# dynext_v2_0.net
KiCad netlist of a schematic drawn in EAGLE
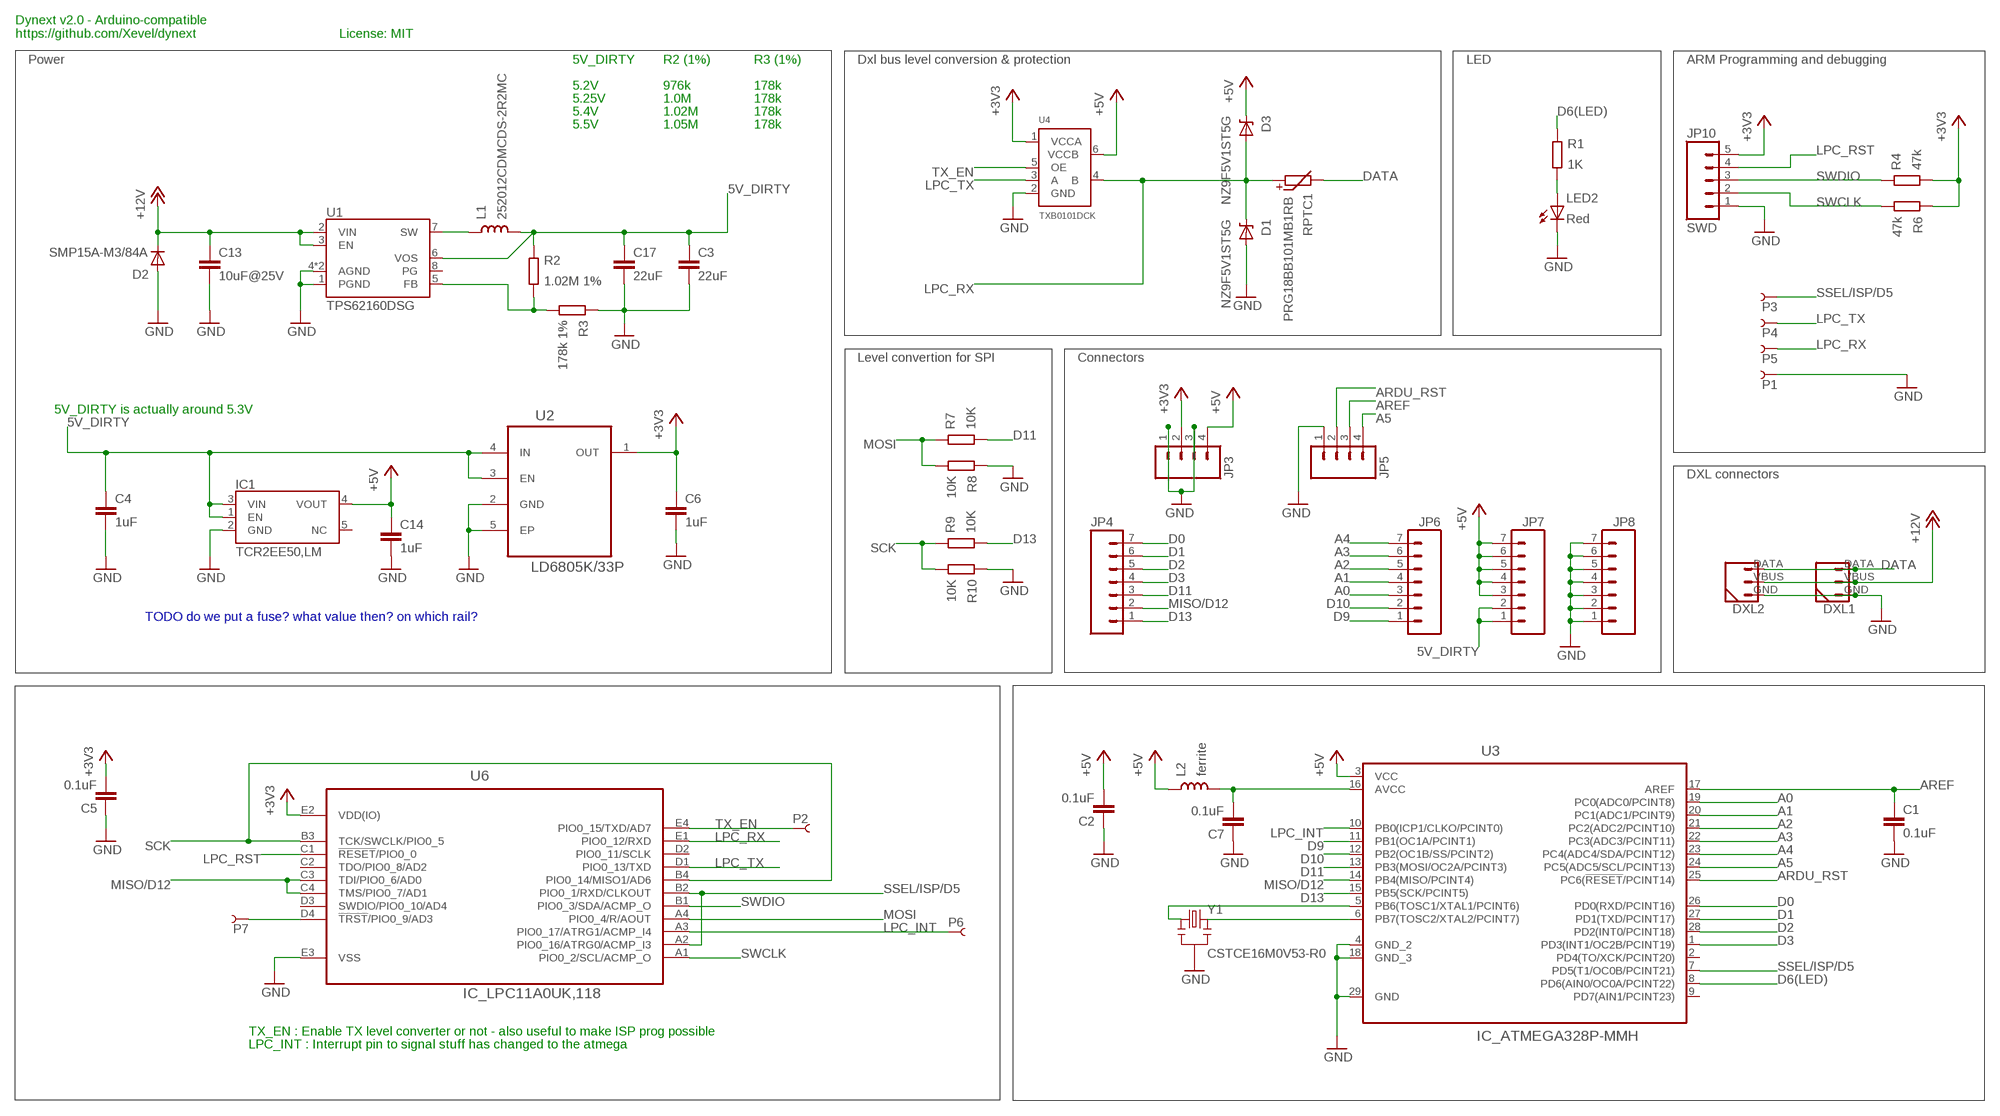
[diagram p0: schematic, sheet 1]

(export (version "E")
  (design (tool "Eeschema 10.0.6"))
  (components
    (comp (ref "C1")
      (value "0.1uF")
      (footprint "eagle-import:0201_N")
      (libsource (lib "eagle-import") (part "C0201"))
    )
    (comp (ref "C2")
      (value "0.1uF")
      (footprint "eagle-import:0201_N")
      (libsource (lib "eagle-import") (part "C0201"))
    )
    (comp (ref "C3")
      (value "22uF")
      (footprint "eagle-import:1206_N")
      (libsource (lib "eagle-import") (part "C1206"))
    )
    (comp (ref "C4")
      (value "1uF")
      (footprint "eagle-import:0402_N")
      (libsource (lib "eagle-import") (part "C0402"))
    )
    (comp (ref "C5")
      (value "0.1uF")
      (footprint "eagle-import:0201_N")
      (libsource (lib "eagle-import") (part "C0201"))
    )
    (comp (ref "C6")
      (value "1uF")
      (footprint "eagle-import:0402_N")
      (libsource (lib "eagle-import") (part "C0402"))
    )
    (comp (ref "C7")
      (value "0.1uF")
      (footprint "eagle-import:0201_N")
      (libsource (lib "eagle-import") (part "C0201"))
    )
    (comp (ref "C13")
      (value "10uF@25V")
      (footprint "eagle-import:0805_N")
      (libsource (lib "eagle-import") (part "C0805"))
    )
    (comp (ref "C14")
      (value "1uF")
      (footprint "eagle-import:0402_N")
      (libsource (lib "eagle-import") (part "C0402"))
    )
    (comp (ref "C17")
      (value "22uF")
      (footprint "eagle-import:1206_N")
      (libsource (lib "eagle-import") (part "C1206"))
    )
    (comp (ref "D1")
      (value "NZ9F5V1ST5G")
      (footprint "eagle-import:SOD-923_N")
      (libsource (lib "eagle-import") (part "DIODE_ZENER-923"))
    )
    (comp (ref "D2")
      (value "SMP15A-M3/84A")
      (footprint "eagle-import:DO-220AA")
      (libsource (lib "eagle-import") (part "DIODE-SMP"))
    )
    (comp (ref "D3")
      (value "NZ9F5V1ST5G")
      (footprint "eagle-import:SOD-923_N")
      (libsource (lib "eagle-import") (part "DIODE_ZENER-923"))
    )
    (comp (ref "DXL1")
      (value "DYNAMIXEL_3POS-R")
      (footprint "eagle-import:DYNAMIXEL_3POS_RIGHT")
      (libsource (lib "eagle-import") (part "DYNAMIXEL_3POS-R"))
    )
    (comp (ref "DXL2")
      (value "DYNAMIXEL_3POS-R")
      (footprint "eagle-import:DYNAMIXEL_3POS_RIGHT")
      (libsource (lib "eagle-import") (part "DYNAMIXEL_3POS-R"))
    )
    (comp (ref "IC1")
      (value "TCR2EE50,LM")
      (footprint "eagle-import:SOT50P160X60-5N")
      (libsource (lib "eagle-import") (part "IC_TCR2EEESV"))
    )
    (comp (ref "JP3")
      (value "M041X04_NO_SILK")
      (footprint "eagle-import:1X04_NO_SILK")
      (libsource (lib "eagle-import") (part "M041X04_NO_SILK"))
    )
    (comp (ref "JP4")
      (value "M07NO_SILK")
      (footprint "eagle-import:1X07_NO_SILK")
      (libsource (lib "eagle-import") (part "M07NO_SILK"))
    )
    (comp (ref "JP5")
      (value "M041X04_NO_SILK")
      (footprint "eagle-import:1X04_NO_SILK")
      (libsource (lib "eagle-import") (part "M041X04_NO_SILK"))
    )
    (comp (ref "JP6")
      (value "M07NO_SILK")
      (footprint "eagle-import:1X07_NO_SILK")
      (libsource (lib "eagle-import") (part "M07NO_SILK"))
    )
    (comp (ref "JP7")
      (value "M07NO_SILK")
      (footprint "eagle-import:1X07_NO_SILK")
      (libsource (lib "eagle-import") (part "M07NO_SILK"))
    )
    (comp (ref "JP8")
      (value "M07SQUARE_ALL")
      (footprint "eagle-import:1X07_SQUARE_ALL")
      (libsource (lib "eagle-import") (part "M07SQUARE_ALL"))
    )
    (comp (ref "JP10")
      (value "SWD")
      (footprint "eagle-import:1X05-1.27MM")
      (libsource (lib "eagle-import") (part "M051.27MM"))
    )
    (comp (ref "L1")
      (value "252012CDMCDS-2R2MC")
      (footprint "eagle-import:1008_N")
      (libsource (lib "eagle-import") (part "L1008"))
    )
    (comp (ref "L2")
      (value "ferrite")
      (footprint "eagle-import:0402_N")
      (libsource (lib "eagle-import") (part "L0402"))
    )
    (comp (ref "LED2")
      (value "Red")
      (footprint "eagle-import:D_0603_N")
      (libsource (lib "eagle-import") (part "LED0603"))
    )
    (comp (ref "P1")
      (value "PIN_SMD_0.8X2")
      (footprint "eagle-import:PIN_SMD_0.8X2")
      (libsource (lib "eagle-import") (part "PIN_SMD_0.8X2"))
    )
    (comp (ref "P2")
      (value "PIN_SMD_1X1")
      (footprint "eagle-import:PIN_SMD_1X1")
      (libsource (lib "eagle-import") (part "PIN_SMD_1X1"))
    )
    (comp (ref "P3")
      (value "PIN_SMD_0.8X2")
      (footprint "eagle-import:PIN_SMD_0.8X2")
      (libsource (lib "eagle-import") (part "PIN_SMD_0.8X2"))
    )
    (comp (ref "P4")
      (value "PIN_SMD_0.8X2")
      (footprint "eagle-import:PIN_SMD_0.8X2")
      (libsource (lib "eagle-import") (part "PIN_SMD_0.8X2"))
    )
    (comp (ref "P5")
      (value "PIN_SMD_0.8X2")
      (footprint "eagle-import:PIN_SMD_0.8X2")
      (libsource (lib "eagle-import") (part "PIN_SMD_0.8X2"))
    )
    (comp (ref "P6")
      (value "PIN_SMD_1X1")
      (footprint "eagle-import:PIN_SMD_1X1")
      (libsource (lib "eagle-import") (part "PIN_SMD_1X1"))
    )
    (comp (ref "P7")
      (value "PIN_SMD_1X1")
      (footprint "eagle-import:PIN_SMD_1X1")
      (libsource (lib "eagle-import") (part "PIN_SMD_1X1"))
    )
    (comp (ref "R1")
      (value "1K")
      (footprint "eagle-import:0201_N")
      (libsource (lib "eagle-import") (part "R0201"))
    )
    (comp (ref "R2")
      (value "1.02M 1%")
      (footprint "eagle-import:0201_N")
      (libsource (lib "eagle-import") (part "R0201"))
    )
    (comp (ref "R3")
      (value "178k 1%")
      (footprint "eagle-import:0201_N")
      (libsource (lib "eagle-import") (part "R0201"))
    )
    (comp (ref "R4")
      (value "47k")
      (footprint "eagle-import:0201_N")
      (libsource (lib "eagle-import") (part "R0201"))
    )
    (comp (ref "R6")
      (value "47k")
      (footprint "eagle-import:0201_N")
      (libsource (lib "eagle-import") (part "R0201"))
    )
    (comp (ref "R7")
      (value "10K")
      (footprint "eagle-import:0201_N")
      (libsource (lib "eagle-import") (part "R0201"))
    )
    (comp (ref "R8")
      (value "10K")
      (footprint "eagle-import:0201_N")
      (libsource (lib "eagle-import") (part "R0201"))
    )
    (comp (ref "R9")
      (value "10K")
      (footprint "eagle-import:0201_N")
      (libsource (lib "eagle-import") (part "R0201"))
    )
    (comp (ref "R10")
      (value "10K")
      (footprint "eagle-import:0201_N")
      (libsource (lib "eagle-import") (part "R0201"))
    )
    (comp (ref "RPTC1")
      (value "PRG18BB101MB1RB")
      (footprint "eagle-import:0603_N")
      (libsource (lib "eagle-import") (part "R-PTC0603"))
    )
    (comp (ref "U1")
      (value "TPS62160DSG")
      (footprint "eagle-import:SON50P200X200X80-9L")
      (libsource (lib "eagle-import") (part "IC_TPS62160DSG_L"))
    )
    (comp (ref "U2")
      (value "LD6805K/33P")
      (footprint "eagle-import:NXP_LD6805")
      (libsource (lib "eagle-import") (part "LD6805K/33P"))
    )
    (comp (ref "U3")
      (value "IC_ATMEGA328P-MMH")
      (footprint "eagle-import:QFN45P400X400X100-29N")
      (fields (field (name "MPN") "ATMEGA328P-MMH"))
      (libsource (lib "eagle-import") (part "IC_ATMEGA328P-MMH"))
    )
    (comp (ref "U4")
      (value "TXB0101DCK")
      (footprint "eagle-import:SC70-6")
      (libsource (lib "eagle-import") (part "TXB0101DCK"))
    )
    (comp (ref "U6")
      (value "IC_LPC11A0UK,118")
      (footprint "eagle-import:BGA20C50P_250X250X65")
      (fields (field (name "MPN") "LPC11A02UK,118"))
      (libsource (lib "eagle-import") (part "IC_LPC11A0?UK,118"))
    )
    (comp (ref "Y1")
      (value "CSTCE16M0V53-R0")
      (footprint "eagle-import:RESONATOR-SMD")
      (libsource (lib "eagle-import") (part "RESONATOR16MHZ"))
    )
  )
  (nets
    (net (code "1") (name "+3V3") (class "Default")
      (node (ref "C5") (pin "2") (pinfunction "2_2") (pintype "passive"))
      (node (ref "C6") (pin "1") (pinfunction "1_1") (pintype "passive"))
      (node (ref "JP10") (pin "5") (pinfunction "5_5") (pintype "passive"))
      (node (ref "JP3") (pin "2") (pinfunction "2_2") (pintype "passive"))
      (node (ref "R4") (pin "1") (pinfunction "1_1") (pintype "passive"))
      (node (ref "R6") (pin "2") (pinfunction "2_2") (pintype "passive"))
      (node (ref "U2") (pin "1") (pinfunction "OUT_1") (pintype "power_in"))
      (node (ref "U4") (pin "1") (pinfunction "VCCA_1") (pintype "bidirectional"))
      (node (ref "U6") (pin "E2") (pinfunction "VDD(IO)_E2") (pintype "power_in"))
    )
    (net (code "2") (name "+5V") (class "Default")
      (node (ref "C14") (pin "1") (pinfunction "1_1") (pintype "passive"))
      (node (ref "C2") (pin "2") (pinfunction "2_2") (pintype "passive"))
      (node (ref "D3") (pin "C") (pinfunction "C_C") (pintype "passive"))
      (node (ref "IC1") (pin "4") (pinfunction "VOUT_4") (pintype "bidirectional"))
      (node (ref "JP3") (pin "4") (pinfunction "4_4") (pintype "passive"))
      (node (ref "JP7") (pin "3") (pinfunction "3_3") (pintype "passive"))
      (node (ref "JP7") (pin "4") (pinfunction "4_4") (pintype "passive"))
      (node (ref "JP7") (pin "5") (pinfunction "5_5") (pintype "passive"))
      (node (ref "JP7") (pin "6") (pinfunction "6_6") (pintype "passive"))
      (node (ref "JP7") (pin "7") (pinfunction "7_7") (pintype "passive"))
      (node (ref "L2") (pin "1") (pinfunction "1_1") (pintype "passive"))
      (node (ref "U3") (pin "3") (pinfunction "VCC_3") (pintype "power_in"))
      (node (ref "U4") (pin "6") (pinfunction "VCCB_6") (pintype "bidirectional"))
    )
    (net (code "3") (name "+12V") (class "Default")
      (node (ref "C13") (pin "1") (pinfunction "1_1") (pintype "passive"))
      (node (ref "D2") (pin "C") (pinfunction "C_C") (pintype "passive"))
      (node (ref "DXL1") (pin "VBUS") (pinfunction "2_VBUS") (pintype "bidirectional"))
      (node (ref "DXL2") (pin "VBUS") (pinfunction "2_VBUS") (pintype "bidirectional"))
      (node (ref "U1") (pin "2") (pinfunction "VIN_2") (pintype "bidirectional"))
      (node (ref "U1") (pin "3") (pinfunction "EN_3") (pintype "input"))
    )
    (net (code "4") (name "/5V_DIRTY") (class "Default")
      (node (ref "C17") (pin "1") (pinfunction "1_1") (pintype "passive"))
      (node (ref "C3") (pin "1") (pinfunction "1_1") (pintype "passive"))
      (node (ref "C4") (pin "1") (pinfunction "1_1") (pintype "passive"))
      (node (ref "IC1") (pin "1") (pinfunction "EN_1") (pintype "bidirectional"))
      (node (ref "IC1") (pin "3") (pinfunction "VIN_3") (pintype "bidirectional"))
      (node (ref "JP7") (pin "1") (pinfunction "1_1") (pintype "passive"))
      (node (ref "JP7") (pin "2") (pinfunction "2_2") (pintype "passive"))
      (node (ref "L1") (pin "2") (pinfunction "2_2") (pintype "passive"))
      (node (ref "R2") (pin "2") (pinfunction "2_2") (pintype "passive"))
      (node (ref "U1") (pin "6") (pinfunction "VOS_6") (pintype "bidirectional"))
      (node (ref "U2") (pin "3") (pinfunction "EN_3") (pintype "passive"))
      (node (ref "U2") (pin "4") (pinfunction "IN_4") (pintype "input"))
    )
    (net (code "5") (name "/A0") (class "Default")
      (node (ref "JP6") (pin "3") (pinfunction "3_3") (pintype "passive"))
      (node (ref "U3") (pin "19") (pinfunction "PC0(ADC0/PCINT8)_19") (pintype "bidirectional"))
    )
    (net (code "6") (name "/A1") (class "Default")
      (node (ref "JP6") (pin "4") (pinfunction "4_4") (pintype "passive"))
      (node (ref "U3") (pin "20") (pinfunction "PC1(ADC1/PCINT9)_20") (pintype "bidirectional"))
    )
    (net (code "7") (name "/A2") (class "Default")
      (node (ref "JP6") (pin "5") (pinfunction "5_5") (pintype "passive"))
      (node (ref "U3") (pin "21") (pinfunction "PC2(ADC2/PCINT10)_21") (pintype "bidirectional"))
    )
    (net (code "8") (name "/A3") (class "Default")
      (node (ref "JP6") (pin "6") (pinfunction "6_6") (pintype "passive"))
      (node (ref "U3") (pin "22") (pinfunction "PC3(ADC3/PCINT11)_22") (pintype "bidirectional"))
    )
    (net (code "9") (name "/A4") (class "Default")
      (node (ref "JP6") (pin "7") (pinfunction "7_7") (pintype "passive"))
      (node (ref "U3") (pin "23") (pinfunction "PC4(ADC4/SDA/PCINT12)_23") (pintype "bidirectional"))
    )
    (net (code "10") (name "/A5") (class "Default")
      (node (ref "JP5") (pin "4") (pinfunction "4_4") (pintype "passive"))
      (node (ref "U3") (pin "24") (pinfunction "PC5(ADC5/SCL/PCINT13)_24") (pintype "bidirectional"))
    )
    (net (code "11") (name "/ARDU_RST") (class "Default")
      (node (ref "JP5") (pin "2") (pinfunction "2_2") (pintype "passive"))
      (node (ref "U3") (pin "25") (pinfunction "PC6(~{RESET}/PCINT14)_25") (pintype "bidirectional"))
    )
    (net (code "12") (name "/AREF") (class "Default")
      (node (ref "C1") (pin "1") (pinfunction "1_1") (pintype "passive"))
      (node (ref "JP5") (pin "3") (pinfunction "3_3") (pintype "passive"))
      (node (ref "U3") (pin "17") (pinfunction "AREF_17") (pintype "passive"))
    )
    (net (code "13") (name "/D0") (class "Default")
      (node (ref "JP4") (pin "7") (pinfunction "7_7") (pintype "passive"))
      (node (ref "U3") (pin "26") (pinfunction "PD0(RXD/PCINT16)_26") (pintype "bidirectional"))
    )
    (net (code "14") (name "/D1") (class "Default")
      (node (ref "JP4") (pin "6") (pinfunction "6_6") (pintype "passive"))
      (node (ref "U3") (pin "27") (pinfunction "PD1(TXD/PCINT17)_27") (pintype "bidirectional"))
    )
    (net (code "15") (name "/D2") (class "Default")
      (node (ref "JP4") (pin "5") (pinfunction "5_5") (pintype "passive"))
      (node (ref "U3") (pin "28") (pinfunction "PD2(INT0/PCINT18)_28") (pintype "bidirectional"))
    )
    (net (code "16") (name "/D3") (class "Default")
      (node (ref "JP4") (pin "4") (pinfunction "4_4") (pintype "passive"))
      (node (ref "U3") (pin "1") (pinfunction "PD3(INT1/OC2B/PCINT19)_1") (pintype "bidirectional"))
    )
    (net (code "17") (name "/D6(LED)") (class "Default")
      (node (ref "R1") (pin "2") (pinfunction "2_2") (pintype "passive"))
      (node (ref "U3") (pin "8") (pinfunction "PD6(AIN0/OC0A/PCINT22)_8") (pintype "bidirectional"))
    )
    (net (code "18") (name "/D9") (class "Default")
      (node (ref "JP6") (pin "1") (pinfunction "1_1") (pintype "passive"))
      (node (ref "U3") (pin "11") (pinfunction "PB1(OC1A/PCINT1)_11") (pintype "bidirectional"))
    )
    (net (code "19") (name "/D10") (class "Default")
      (node (ref "JP6") (pin "2") (pinfunction "2_2") (pintype "passive"))
      (node (ref "U3") (pin "12") (pinfunction "PB2(OC1B/SS/PCINT2)_12") (pintype "bidirectional"))
    )
    (net (code "20") (name "/D11") (class "Default")
      (node (ref "JP4") (pin "3") (pinfunction "3_3") (pintype "passive"))
      (node (ref "R7") (pin "1") (pinfunction "1_1") (pintype "passive"))
      (node (ref "U3") (pin "13") (pinfunction "PB3(MOSI/OC2A/PCINT3)_13") (pintype "bidirectional"))
    )
    (net (code "21") (name "/D13") (class "Default")
      (node (ref "JP4") (pin "1") (pinfunction "1_1") (pintype "passive"))
      (node (ref "R9") (pin "1") (pinfunction "1_1") (pintype "passive"))
      (node (ref "U3") (pin "15") (pinfunction "PB5(SCK/PCINT5)_15") (pintype "bidirectional"))
    )
    (net (code "22") (name "/DATA") (class "Default")
      (node (ref "DXL1") (pin "DATA") (pinfunction "3_DATA") (pintype "bidirectional"))
      (node (ref "DXL2") (pin "DATA") (pinfunction "3_DATA") (pintype "bidirectional"))
      (node (ref "RPTC1") (pin "2") (pinfunction "2_2") (pintype "passive"))
    )
    (net (code "23") (name "/LPC_INT") (class "Default")
      (node (ref "P6") (pin "P$1") (pinfunction "1_P$1") (pintype "bidirectional"))
      (node (ref "U3") (pin "10") (pinfunction "PB0(ICP1/CLKO/PCINT0)_10") (pintype "bidirectional"))
      (node (ref "U6") (pin "A3") (pinfunction "PIO0_17/ATRG1/ACMP_I4_A3") (pintype "bidirectional"))
    )
    (net (code "24") (name "/LPC_RST") (class "Default")
      (node (ref "JP10") (pin "4") (pinfunction "4_4") (pintype "passive"))
      (node (ref "U6") (pin "C1") (pinfunction "~{RESET}/PIO0_0_C1") (pintype "passive"))
    )
    (net (code "25") (name "/LPC_RX") (class "Default")
      (node (ref "D1") (pin "C") (pinfunction "C_C") (pintype "passive"))
      (node (ref "D3") (pin "A") (pinfunction "A_A") (pintype "passive"))
      (node (ref "P5") (pin "PIN") (pinfunction "1_PIN") (pintype "bidirectional"))
      (node (ref "RPTC1") (pin "1") (pinfunction "1_1") (pintype "passive"))
      (node (ref "U4") (pin "4") (pinfunction "B_4") (pintype "bidirectional"))
      (node (ref "U6") (pin "E1") (pinfunction "PIO0_12/RXD_E1") (pintype "bidirectional"))
    )
    (net (code "26") (name "/LPC_TX") (class "Default")
      (node (ref "P4") (pin "PIN") (pinfunction "1_PIN") (pintype "bidirectional"))
      (node (ref "U4") (pin "3") (pinfunction "A_3") (pintype "bidirectional"))
      (node (ref "U6") (pin "D1") (pinfunction "PIO0_13/TXD_D1") (pintype "bidirectional"))
    )
    (net (code "27") (name "/MISO{slash}D12") (class "Default")
      (node (ref "JP4") (pin "2") (pinfunction "2_2") (pintype "passive"))
      (node (ref "U3") (pin "14") (pinfunction "PB4(MISO/PCINT4)_14") (pintype "bidirectional"))
      (node (ref "U6") (pin "C3") (pinfunction "TDI/PIO0_6/AD0_C3") (pintype "passive"))
      (node (ref "U6") (pin "C4") (pinfunction "TMS/PIO0_7/AD1_C4") (pintype "passive"))
    )
    (net (code "28") (name "/MOSI") (class "Default")
      (node (ref "R7") (pin "2") (pinfunction "2_2") (pintype "passive"))
      (node (ref "R8") (pin "1") (pinfunction "1_1") (pintype "passive"))
      (node (ref "U6") (pin "A4") (pinfunction "PIO0_4/R/AOUT_A4") (pintype "bidirectional"))
    )
    (net (code "29") (name "/SCK") (class "Default")
      (node (ref "R10") (pin "1") (pinfunction "1_1") (pintype "passive"))
      (node (ref "R9") (pin "2") (pinfunction "2_2") (pintype "passive"))
      (node (ref "U6") (pin "B3") (pinfunction "TCK/SWCLK/PIO0_5_B3") (pintype "passive"))
      (node (ref "U6") (pin "B4") (pinfunction "PIO0_14/MISO1/AD6_B4") (pintype "bidirectional"))
    )
    (net (code "30") (name "/SSEL{slash}ISP{slash}D5") (class "Default")
      (node (ref "P3") (pin "PIN") (pinfunction "1_PIN") (pintype "bidirectional"))
      (node (ref "U3") (pin "7") (pinfunction "PD5(T1/OC0B/PCINT21)_7") (pintype "bidirectional"))
      (node (ref "U6") (pin "A2") (pinfunction "PIO0_16/ATRG0/ACMP_I3_A2") (pintype "bidirectional"))
      (node (ref "U6") (pin "B2") (pinfunction "PIO0_1/RXD/CLKOUT_B2") (pintype "bidirectional"))
    )
    (net (code "31") (name "/SWCLK") (class "Default")
      (node (ref "JP10") (pin "2") (pinfunction "2_2") (pintype "passive"))
      (node (ref "R6") (pin "1") (pinfunction "1_1") (pintype "passive"))
      (node (ref "U6") (pin "A1") (pinfunction "PIO0_2/SCL/ACMP_O_A1") (pintype "bidirectional"))
    )
    (net (code "32") (name "/SWDIO") (class "Default")
      (node (ref "JP10") (pin "3") (pinfunction "3_3") (pintype "passive"))
      (node (ref "R4") (pin "2") (pinfunction "2_2") (pintype "passive"))
      (node (ref "U6") (pin "B1") (pinfunction "PIO0_3/SDA/ACMP_O_B1") (pintype "bidirectional"))
    )
    (net (code "33") (name "/TX_EN") (class "Default")
      (node (ref "P2") (pin "P$1") (pinfunction "1_P$1") (pintype "bidirectional"))
      (node (ref "U4") (pin "5") (pinfunction "OE_5") (pintype "bidirectional"))
      (node (ref "U6") (pin "E4") (pinfunction "PIO0_15/TXD/AD7_E4") (pintype "bidirectional"))
    )
    (net (code "34") (name "GND") (class "Default")
      (node (ref "C1") (pin "2") (pinfunction "2_2") (pintype "passive"))
      (node (ref "C13") (pin "2") (pinfunction "2_2") (pintype "passive"))
      (node (ref "C14") (pin "2") (pinfunction "2_2") (pintype "passive"))
      (node (ref "C17") (pin "2") (pinfunction "2_2") (pintype "passive"))
      (node (ref "C2") (pin "1") (pinfunction "1_1") (pintype "passive"))
      (node (ref "C3") (pin "2") (pinfunction "2_2") (pintype "passive"))
      (node (ref "C4") (pin "2") (pinfunction "2_2") (pintype "passive"))
      (node (ref "C5") (pin "1") (pinfunction "1_1") (pintype "passive"))
      (node (ref "C6") (pin "2") (pinfunction "2_2") (pintype "passive"))
      (node (ref "C7") (pin "1") (pinfunction "1_1") (pintype "passive"))
      (node (ref "D1") (pin "A") (pinfunction "A_A") (pintype "passive"))
      (node (ref "D2") (pin "A") (pinfunction "A_A") (pintype "passive"))
      (node (ref "DXL1") (pin "GND") (pinfunction "1_GND") (pintype "bidirectional"))
      (node (ref "DXL2") (pin "GND") (pinfunction "1_GND") (pintype "bidirectional"))
      (node (ref "IC1") (pin "2") (pinfunction "GND_2") (pintype "power_in"))
      (node (ref "JP10") (pin "1") (pinfunction "1_1") (pintype "passive"))
      (node (ref "JP3") (pin "1") (pinfunction "1_1") (pintype "passive"))
      (node (ref "JP3") (pin "3") (pinfunction "3_3") (pintype "passive"))
      (node (ref "JP5") (pin "1") (pinfunction "1_1") (pintype "passive"))
      (node (ref "JP8") (pin "1") (pinfunction "1_1") (pintype "passive"))
      (node (ref "JP8") (pin "2") (pinfunction "2_2") (pintype "passive"))
      (node (ref "JP8") (pin "3") (pinfunction "3_3") (pintype "passive"))
      (node (ref "JP8") (pin "4") (pinfunction "4_4") (pintype "passive"))
      (node (ref "JP8") (pin "5") (pinfunction "5_5") (pintype "passive"))
      (node (ref "JP8") (pin "6") (pinfunction "6_6") (pintype "passive"))
      (node (ref "JP8") (pin "7") (pinfunction "7_7") (pintype "passive"))
      (node (ref "LED2") (pin "C") (pinfunction "C_C") (pintype "passive"))
      (node (ref "P1") (pin "PIN") (pinfunction "1_PIN") (pintype "bidirectional"))
      (node (ref "R10") (pin "2") (pinfunction "2_2") (pintype "passive"))
      (node (ref "R3") (pin "2") (pinfunction "2_2") (pintype "passive"))
      (node (ref "R8") (pin "2") (pinfunction "2_2") (pintype "passive"))
      (node (ref "U1") (pin "1") (pinfunction "PGND_1") (pintype "input"))
      (node (ref "U1") (pin "4") (pinfunction "AGND_4") (pintype "input"))
      (node (ref "U1") (pin "9") (pinfunction "AGND_9") (pintype "input"))
      (node (ref "U2") (pin "2") (pinfunction "GND_2") (pintype "power_in"))
      (node (ref "U2") (pin "5") (pinfunction "EP_5") (pintype "passive"))
      (node (ref "U3") (pin "18") (pinfunction "GND_3_18") (pintype "power_in"))
      (node (ref "U3") (pin "29") (pinfunction "GND_29") (pintype "power_in"))
      (node (ref "U3") (pin "4") (pinfunction "GND_2_4") (pintype "power_in"))
      (node (ref "U4") (pin "2") (pinfunction "GND_2") (pintype "bidirectional"))
      (node (ref "U6") (pin "E3") (pinfunction "VSS_E3") (pintype "power_in"))
      (node (ref "Y1") (pin "2") (pinfunction "2_2") (pintype "passive"))
    )
    (net (code "35") (name "Net-(LED2-PadA)") (class "Default")
      (node (ref "LED2") (pin "A") (pinfunction "A_A") (pintype "passive"))
      (node (ref "R1") (pin "1") (pinfunction "1_1") (pintype "passive"))
    )
    (net (code "36") (name "Net-(P7-1)") (class "Default")
      (node (ref "P7") (pin "P$1") (pinfunction "1_P$1") (pintype "bidirectional"))
      (node (ref "U6") (pin "D4") (pinfunction "~{TRST}/PIO0_9/AD3_D4") (pintype "passive"))
    )
    (net (code "37") (name "Net-(U1-FB)") (class "Default")
      (node (ref "R2") (pin "1") (pinfunction "1_1") (pintype "passive"))
      (node (ref "R3") (pin "1") (pinfunction "1_1") (pintype "passive"))
      (node (ref "U1") (pin "5") (pinfunction "FB_5") (pintype "bidirectional"))
    )
    (net (code "38") (name "Net-(U1-SW)") (class "Default")
      (node (ref "L1") (pin "1") (pinfunction "1_1") (pintype "passive"))
      (node (ref "U1") (pin "7") (pinfunction "SW_7") (pintype "bidirectional"))
    )
    (net (code "39") (name "Net-(U3-AVCC)") (class "Default")
      (node (ref "C7") (pin "2") (pinfunction "2_2") (pintype "passive"))
      (node (ref "L2") (pin "2") (pinfunction "2_2") (pintype "passive"))
      (node (ref "U3") (pin "16") (pinfunction "AVCC_16") (pintype "power_in"))
    )
    (net (code "40") (name "Net-(U3-PB6(TOSC1{slash}XTAL1{slash}PCINT6))") (class "Default")
      (node (ref "U3") (pin "5") (pinfunction "PB6(TOSC1/XTAL1/PCINT6)_5") (pintype "bidirectional"))
      (node (ref "Y1") (pin "1") (pinfunction "1_1") (pintype "passive"))
    )
    (net (code "41") (name "Net-(U3-PB7(TOSC2{slash}XTAL2{slash}PCINT7))") (class "Default")
      (node (ref "U3") (pin "6") (pinfunction "PB7(TOSC2/XTAL2/PCINT7)_6") (pintype "bidirectional"))
      (node (ref "Y1") (pin "3") (pinfunction "3_3") (pintype "passive"))
    )
    (net (code "42") (name "unconnected-(IC1-NC-Pad5)") (class "Default")
      (node (ref "IC1") (pin "5") (pinfunction "NC_5") (pintype "no_connect"))
    )
    (net (code "43") (name "unconnected-(U1-PG-Pad8)") (class "Default")
      (node (ref "U1") (pin "8") (pinfunction "PG_8") (pintype "bidirectional"))
    )
    (net (code "44") (name "unconnected-(U3-PD4(TO{slash}XCK{slash}PCINT20)-Pad2)") (class "Default")
      (node (ref "U3") (pin "2") (pinfunction "PD4(TO/XCK/PCINT20)_2") (pintype "bidirectional"))
    )
    (net (code "45") (name "unconnected-(U3-PD7(AIN1{slash}PCINT23)-Pad9)") (class "Default")
      (node (ref "U3") (pin "9") (pinfunction "PD7(AIN1/PCINT23)_9") (pintype "bidirectional"))
    )
    (net (code "46") (name "unconnected-(U6-PIO0_11{slash}SCLK-PadD2)") (class "Default")
      (node (ref "U6") (pin "D2") (pinfunction "PIO0_11/SCLK_D2") (pintype "bidirectional"))
    )
    (net (code "47") (name "unconnected-(U6-SWDIO{slash}PIO0_10{slash}AD4-PadD3)") (class "Default")
      (node (ref "U6") (pin "D3") (pinfunction "SWDIO/PIO0_10/AD4_D3") (pintype "passive"))
    )
    (net (code "48") (name "unconnected-(U6-TDO{slash}PIO0_8{slash}AD2-PadC2)") (class "Default")
      (node (ref "U6") (pin "C2") (pinfunction "TDO/PIO0_8/AD2_C2") (pintype "passive"))
    )
  )
)
